# RTL-SDR.net
KiCad netlist of a schematic drawn in Altium Designer
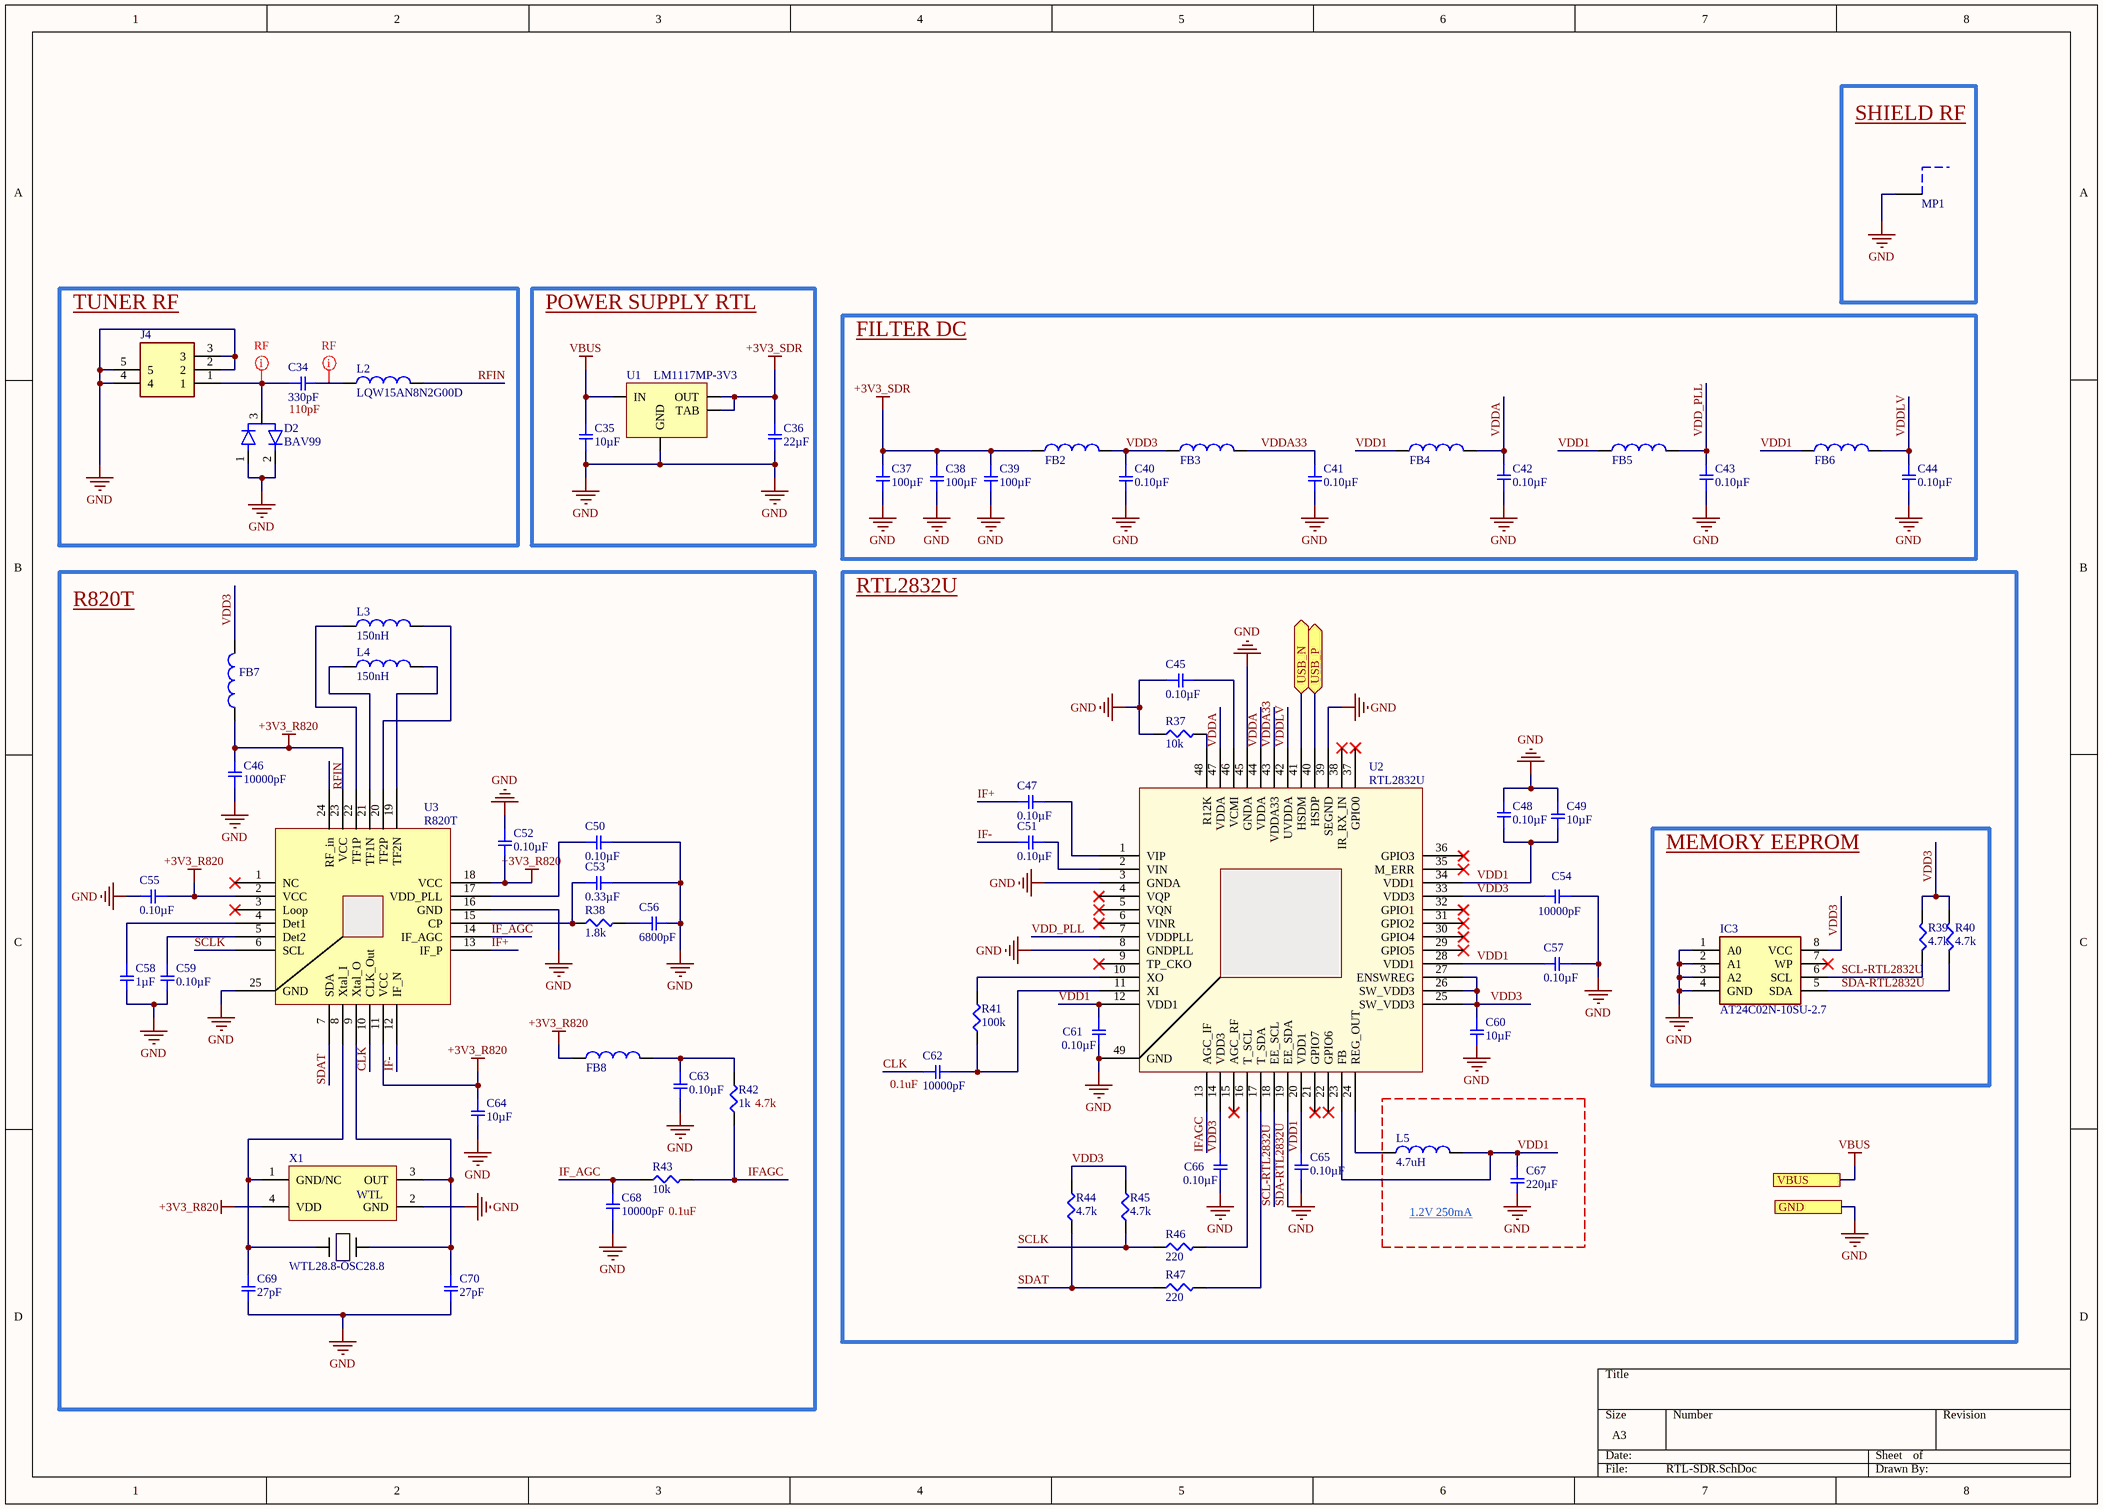
[diagram p0: RTL-SDR.SchDoc]

(export (version "E")
  (design (tool "Eeschema 10.0.6"))
  (components
    (comp (ref "C34")
      (value "330pF")
      (footprint "SMD-0402C")
      (description "CAP CER 330PF 25V NP0 0402")
      (fields
        (field (name "PART NUMBER") "GRM1555C1E331JA01D")
        (field (name "DIGI-KEY PART NUMBER") "490-8176-1-ND")
      )
      (libsource (lib "cap_murata") (part "CAPACITOR"))
    )
    (comp (ref "C35")
      (value "10µF")
      (footprint "SMD-0805C")
      (description "CAP CER 10UF 16V X6S 0805")
      (fields
        (field (name "PART NUMBER") "GRT21BC81C106KE01L")
        (field (name "DIGI-KEY PART NUMBER") "490-12343-1-ND")
      )
      (libsource (lib "cap_murata") (part "CAPACITOR"))
    )
    (comp (ref "C36")
      (value "22µF")
      (footprint "SMD-0805C")
      (description "CAP CER 22UF 16V X5R 0805")
      (fields
        (field (name "PART NUMBER") "GRT21BR61C226ME13L")
        (field (name "DIGI-KEY PART NUMBER") "490-12383-1-ND")
      )
      (libsource (lib "cap_murata") (part "CAPACITOR"))
    )
    (comp (ref "C37")
      (value "100µF")
      (footprint "SMD-1210C")
      (description "CAP CER 100UF 6.3V X7S 1210")
      (fields
        (field (name "PART NUMBER") "GRM32EC70J107ME15L")
        (field (name "DIGI-KEY PART NUMBER") "490-10530-1-ND")
      )
      (libsource (lib "cap_murata") (part "CAPACITOR"))
    )
    (comp (ref "C38")
      (value "100µF")
      (footprint "SMD-1210C")
      (description "CAP CER 100UF 6.3V X7S 1210")
      (fields
        (field (name "PART NUMBER") "GRM32EC70J107ME15L")
        (field (name "DIGI-KEY PART NUMBER") "490-10530-1-ND")
      )
      (libsource (lib "cap_murata") (part "CAPACITOR"))
    )
    (comp (ref "C39")
      (value "100µF")
      (footprint "SMD-1210C")
      (description "CAP CER 100UF 6.3V X7S 1210")
      (fields
        (field (name "PART NUMBER") "GRM32EC70J107ME15L")
        (field (name "DIGI-KEY PART NUMBER") "490-10530-1-ND")
      )
      (libsource (lib "cap_murata") (part "CAPACITOR"))
    )
    (comp (ref "C40")
      (value "0.10µF")
      (footprint "SMD-0402C")
      (description "CAP CER 0.1UF 16V X7R 0402")
      (fields
        (field (name "PART NUMBER") "GCM155R71C104KA55J")
        (field (name "DIGI-KEY PART NUMBER") "490-7998-1-ND")
      )
      (libsource (lib "cap_murata") (part "CAPACITOR"))
    )
    (comp (ref "C41")
      (value "0.10µF")
      (footprint "SMD-0402C")
      (description "CAP CER 0.1UF 16V X7R 0402")
      (fields
        (field (name "PART NUMBER") "GCM155R71C104KA55J")
        (field (name "DIGI-KEY PART NUMBER") "490-7998-1-ND")
      )
      (libsource (lib "cap_murata") (part "CAPACITOR"))
    )
    (comp (ref "C42")
      (value "0.10µF")
      (footprint "SMD-0402C")
      (description "CAP CER 0.1UF 16V X7R 0402")
      (fields
        (field (name "PART NUMBER") "GCM155R71C104KA55J")
        (field (name "DIGI-KEY PART NUMBER") "490-7998-1-ND")
      )
      (libsource (lib "cap_murata") (part "CAPACITOR"))
    )
    (comp (ref "C43")
      (value "0.10µF")
      (footprint "SMD-0402C")
      (description "CAP CER 0.1UF 16V X7R 0402")
      (fields
        (field (name "PART NUMBER") "GCM155R71C104KA55J")
        (field (name "DIGI-KEY PART NUMBER") "490-7998-1-ND")
      )
      (libsource (lib "cap_murata") (part "CAPACITOR"))
    )
    (comp (ref "C44")
      (value "0.10µF")
      (footprint "SMD-0402C")
      (description "CAP CER 0.1UF 16V X7R 0402")
      (fields
        (field (name "PART NUMBER") "GCM155R71C104KA55J")
        (field (name "DIGI-KEY PART NUMBER") "490-7998-1-ND")
      )
      (libsource (lib "cap_murata") (part "CAPACITOR"))
    )
    (comp (ref "C45")
      (value "0.10µF")
      (footprint "SMD-0402C")
      (description "CAP CER 0.1UF 16V X7R 0402")
      (fields
        (field (name "PART NUMBER") "GCM155R71C104KA55J")
        (field (name "DIGI-KEY PART NUMBER") "490-7998-1-ND")
      )
      (libsource (lib "cap_murata") (part "CAPACITOR"))
    )
    (comp (ref "C46")
      (value "10000pF")
      (footprint "SMD-0402C")
      (description "CAP CER 10000PF 16V X7R 0402")
      (fields
        (field (name "PART NUMBER") "GRM155R71C103KA01J")
        (field (name "DIGI-KEY PART NUMBER") "490-6326-1-ND")
      )
      (libsource (lib "cap_murata") (part "CAPACITOR"))
    )
    (comp (ref "C47")
      (value "0.10µF")
      (footprint "SMD-0402C")
      (description "CAP CER 0.1UF 16V X7R 0402")
      (fields
        (field (name "PART NUMBER") "GCM155R71C104KA55J")
        (field (name "DIGI-KEY PART NUMBER") "490-7998-1-ND")
      )
      (libsource (lib "cap_murata") (part "CAPACITOR"))
    )
    (comp (ref "C48")
      (value "0.10µF")
      (footprint "SMD-0402C")
      (description "CAP CER 0.1UF 16V X7R 0402")
      (fields
        (field (name "PART NUMBER") "GCM155R71C104KA55J")
        (field (name "DIGI-KEY PART NUMBER") "490-7998-1-ND")
      )
      (libsource (lib "cap_murata") (part "CAPACITOR"))
    )
    (comp (ref "C49")
      (value "10µF")
      (footprint "SMD-0603C")
      (description "CAP CER 10UF 16V X6S 0603")
      (fields
        (field (name "PART NUMBER") "GRT188C81C106ME13D")
        (field (name "DIGI-KEY PART NUMBER") "490-12286-1-ND")
      )
      (libsource (lib "cap_murata") (part "CAPACITOR"))
    )
    (comp (ref "C50")
      (value "0.10µF")
      (footprint "SMD-0402C")
      (description "CAP CER 0.1UF 16V X7R 0402")
      (fields
        (field (name "PART NUMBER") "GCM155R71C104KA55J")
        (field (name "DIGI-KEY PART NUMBER") "490-7998-1-ND")
      )
      (libsource (lib "cap_murata") (part "CAPACITOR"))
    )
    (comp (ref "C51")
      (value "0.10µF")
      (footprint "SMD-0402C")
      (description "CAP CER 0.1UF 16V X7R 0402")
      (fields
        (field (name "PART NUMBER") "GCM155R71C104KA55J")
        (field (name "DIGI-KEY PART NUMBER") "490-7998-1-ND")
      )
      (libsource (lib "cap_murata") (part "CAPACITOR"))
    )
    (comp (ref "C52")
      (value "0.10µF")
      (footprint "SMD-0402C")
      (description "CAP CER 0.1UF 16V X7R 0402")
      (fields
        (field (name "PART NUMBER") "GCM155R71C104KA55J")
        (field (name "DIGI-KEY PART NUMBER") "490-7998-1-ND")
      )
      (libsource (lib "cap_murata") (part "CAPACITOR"))
    )
    (comp (ref "C53")
      (value "0.33µF")
      (footprint "SMD-0402C")
      (description "CAP CER 0.33UF 10V X5R 0402")
      (fields
        (field (name "PART NUMBER") "GRM155R61A334KE15D")
        (field (name "DIGI-KEY PART NUMBER") "490-3263-1-ND")
      )
      (libsource (lib "cap_murata") (part "CAPACITOR"))
    )
    (comp (ref "C54")
      (value "10000pF")
      (footprint "SMD-0402C")
      (description "CAP CER 10000PF 16V X7R 0402")
      (fields
        (field (name "PART NUMBER") "GRM155R71C103KA01J")
        (field (name "DIGI-KEY PART NUMBER") "490-6326-1-ND")
      )
      (libsource (lib "cap_murata") (part "CAPACITOR"))
    )
    (comp (ref "C55")
      (value "0.10µF")
      (footprint "SMD-0402C")
      (description "CAP CER 0.1UF 16V X7R 0402")
      (fields
        (field (name "PART NUMBER") "GCM155R71C104KA55J")
        (field (name "DIGI-KEY PART NUMBER") "490-7998-1-ND")
      )
      (libsource (lib "cap_murata") (part "CAPACITOR"))
    )
    (comp (ref "C56")
      (value "6800pF")
      (footprint "SMD-0402C")
      (description "CAP CER 6800PF 25V X7R 0402")
      (fields
        (field (name "PART NUMBER") "GRM155R71E682KA01D")
        (field (name "DIGI-KEY PART NUMBER") "490-1310-1-ND")
      )
      (libsource (lib "cap_murata") (part "CAPACITOR"))
    )
    (comp (ref "C57")
      (value "0.10µF")
      (footprint "SMD-0402C")
      (description "CAP CER 0.1UF 16V X7R 0402")
      (fields
        (field (name "PART NUMBER") "GCM155R71C104KA55J")
        (field (name "DIGI-KEY PART NUMBER") "490-7998-1-ND")
      )
      (libsource (lib "cap_murata") (part "CAPACITOR"))
    )
    (comp (ref "C58")
      (value "1µF")
      (footprint "SMD-0402C")
      (description "CAP CER 1UF 25V X5R 0402")
      (fields
        (field (name "PART NUMBER") "GRM155R61E105MA12D")
        (field (name "DIGI-KEY PART NUMBER") "490-10018-1-ND")
      )
      (libsource (lib "cap_murata") (part "CAPACITOR"))
    )
    (comp (ref "C59")
      (value "0.10µF")
      (footprint "SMD-0402C")
      (description "CAP CER 0.1UF 16V X7R 0402")
      (fields
        (field (name "PART NUMBER") "GCM155R71C104KA55J")
        (field (name "DIGI-KEY PART NUMBER") "490-7998-1-ND")
      )
      (libsource (lib "cap_murata") (part "CAPACITOR"))
    )
    (comp (ref "C60")
      (value "10µF")
      (footprint "SMD-0603C")
      (description "CAP CER 10UF 16V X6S 0603")
      (fields
        (field (name "PART NUMBER") "GRT188C81C106ME13D")
        (field (name "DIGI-KEY PART NUMBER") "490-12286-1-ND")
      )
      (libsource (lib "cap_murata") (part "CAPACITOR"))
    )
    (comp (ref "C61")
      (value "0.10µF")
      (footprint "SMD-0402C")
      (description "CAP CER 0.1UF 16V X7R 0402")
      (fields
        (field (name "PART NUMBER") "GCM155R71C104KA55J")
        (field (name "DIGI-KEY PART NUMBER") "490-7998-1-ND")
      )
      (libsource (lib "cap_murata") (part "CAPACITOR"))
    )
    (comp (ref "C62")
      (value "10000pF")
      (footprint "SMD-0402C")
      (description "CAP CER 10000PF 16V X7R 0402")
      (fields
        (field (name "PART NUMBER") "GRM155R71C103KA01D")
        (field (name "DIGI-KEY PART NUMBER") "490-1313-1-ND")
      )
      (libsource (lib "cap_murata") (part "CAPACITOR"))
    )
    (comp (ref "C63")
      (value "0.10µF")
      (footprint "SMD-0402C")
      (description "CAP CER 0.1UF 16V X7R 0402")
      (fields
        (field (name "PART NUMBER") "GCM155R71C104KA55J")
        (field (name "DIGI-KEY PART NUMBER") "490-7998-1-ND")
      )
      (libsource (lib "cap_murata") (part "CAPACITOR"))
    )
    (comp (ref "C64")
      (value "10µF")
      (footprint "SMD-0805C")
      (description "CAP CER 10UF 16V X6S 0805")
      (fields
        (field (name "PART NUMBER") "GRT21BC81C106KE01L")
        (field (name "DIGI-KEY PART NUMBER") "490-12343-1-ND")
      )
      (libsource (lib "cap_murata") (part "CAPACITOR"))
    )
    (comp (ref "C65")
      (value "0.10µF")
      (footprint "SMD-0402C")
      (description "CAP CER 0.1UF 16V X7R 0402")
      (fields
        (field (name "PART NUMBER") "GCM155R71C104KA55J")
        (field (name "DIGI-KEY PART NUMBER") "490-7998-1-ND")
      )
      (libsource (lib "cap_murata") (part "CAPACITOR"))
    )
    (comp (ref "C66")
      (value "0.10µF")
      (footprint "SMD-0402C")
      (description "CAP CER 0.1UF 16V X7R 0402")
      (fields
        (field (name "PART NUMBER") "GCM155R71C104KA55J")
        (field (name "DIGI-KEY PART NUMBER") "490-7998-1-ND")
      )
      (libsource (lib "cap_murata") (part "CAPACITOR"))
    )
    (comp (ref "C67")
      (value "220µF")
      (footprint "SMD-1210C")
      (description "CAP CER 220UF 4V X6S 1210")
      (fields
        (field (name "PART NUMBER") "GRM32EC80G227ME05L")
        (field (name "DIGI-KEY PART NUMBER") "490-13973-1-ND")
      )
      (libsource (lib "cap_murata") (part "CAPACITOR"))
    )
    (comp (ref "C68")
      (value "10000pF")
      (footprint "SMD-0402C")
      (description "CAP CER 10000PF 16V X7R 0402")
      (fields
        (field (name "PART NUMBER") "GRM155R71C103KA01J")
        (field (name "DIGI-KEY PART NUMBER") "490-6326-1-ND")
      )
      (libsource (lib "cap_murata") (part "CAPACITOR"))
    )
    (comp (ref "C69")
      (value "27pF")
      (footprint "SMD-0402C")
      (description "CAP CER 27PF 25V NP0 0402")
      (fields
        (field (name "PART NUMBER") "GRM1555C1E270JA01D")
        (field (name "DIGI-KEY PART NUMBER") "490-6176-1-ND")
      )
      (libsource (lib "cap_murata") (part "CAPACITOR"))
    )
    (comp (ref "C70")
      (value "27pF")
      (footprint "SMD-0402C")
      (description "CAP CER 27PF 25V NP0 0402")
      (fields
        (field (name "PART NUMBER") "GRM1555C1E270JA01D")
        (field (name "DIGI-KEY PART NUMBER") "490-6176-1-ND")
      )
      (libsource (lib "cap_murata") (part "CAPACITOR"))
    )
    (comp (ref "D2")
      (value "BAV99")
      (footprint "DIO_BAV99")
      (fields (field (name "MF") "ON Semiconductor"))
      (libsource (lib "DSD_Aerobits_RPI4_OLED") (part "BAV99"))
    )
    (comp (ref "FB2")
      (value "10Ohm")
      (footprint "WE-CBA_0402_L1W0.5H0.5_HC")
      (description "WE-CBA SMT EMI Suppression Ferrite Bead, size 0402, 10Ohm, 1.5A")
      (fields
        (field (name "MANUFACTURER PART NUMBER") "782423100")
        (field (name "MANUFACTURER") "Wurth Elektronik")
      )
      (libsource (lib "Altium_WE-CBA (rev22d)") (part "782423100"))
    )
    (comp (ref "FB3")
      (value "10Ohm")
      (footprint "WE-CBA_0402_L1W0.5H0.5_HC")
      (description "WE-CBA SMT EMI Suppression Ferrite Bead, size 0402, 10Ohm, 1.5A")
      (fields
        (field (name "MANUFACTURER PART NUMBER") "782423100")
        (field (name "MANUFACTURER") "Wurth Elektronik")
      )
      (libsource (lib "Altium_WE-CBA (rev22d)") (part "782423100"))
    )
    (comp (ref "FB4")
      (value "10Ohm")
      (footprint "WE-CBA_0402_L1W0.5H0.5_HC")
      (description "WE-CBA SMT EMI Suppression Ferrite Bead, size 0402, 10Ohm, 1.5A")
      (fields
        (field (name "MANUFACTURER PART NUMBER") "782423100")
        (field (name "MANUFACTURER") "Wurth Elektronik")
      )
      (libsource (lib "Altium_WE-CBA (rev22d)") (part "782423100"))
    )
    (comp (ref "FB5")
      (value "10Ohm")
      (footprint "WE-CBA_0402_L1W0.5H0.5_HC")
      (description "WE-CBA SMT EMI Suppression Ferrite Bead, size 0402, 10Ohm, 1.5A")
      (fields
        (field (name "MANUFACTURER PART NUMBER") "782423100")
        (field (name "MANUFACTURER") "Wurth Elektronik")
      )
      (libsource (lib "Altium_WE-CBA (rev22d)") (part "782423100"))
    )
    (comp (ref "FB6")
      (value "10Ohm")
      (footprint "WE-CBA_0402_L1W0.5H0.5_HC")
      (description "WE-CBA SMT EMI Suppression Ferrite Bead, size 0402, 10Ohm, 1.5A")
      (fields
        (field (name "MANUFACTURER PART NUMBER") "782423100")
        (field (name "MANUFACTURER") "Wurth Elektronik")
      )
      (libsource (lib "Altium_WE-CBA (rev22d)") (part "782423100"))
    )
    (comp (ref "FB7")
      (value "10Ohm")
      (footprint "WE-CBA_0402_L1W0.5H0.5_HC")
      (description "WE-CBA SMT EMI Suppression Ferrite Bead, size 0402, 10Ohm, 1.5A")
      (fields
        (field (name "MANUFACTURER PART NUMBER") "782423100")
        (field (name "MANUFACTURER") "Wurth Elektronik")
      )
      (libsource (lib "Altium_WE-CBA (rev22d)") (part "782423100"))
    )
    (comp (ref "FB8")
      (value "10Ohm")
      (footprint "WE-CBA_0402_L1W0.5H0.5_HC")
      (description "WE-CBA SMT EMI Suppression Ferrite Bead, size 0402, 10Ohm, 1.5A")
      (fields
        (field (name "MANUFACTURER PART NUMBER") "782423100")
        (field (name "MANUFACTURER") "Wurth Elektronik")
      )
      (libsource (lib "Altium_WE-CBA (rev22d)") (part "782423100"))
    )
    (comp (ref "IC3")
      (value "AT24C02N-10SU-2.7")
      (footprint "SamacSys:SOIC127P600X175-8N")
      (description "Integrated Circuit")
      (libsource (lib "SamacSys") (part "AT24C02N-10SU-2.7"))
    )
    (comp (ref "J4")
      (value "SMA-J-P-H-RA-TH1")
      (footprint "SamacSys:SMAJPHRATH1")
      (description "Connector")
      (fields (field (name "MOUSER PART NUMBER") "200-SMAJPHRATH1"))
      (libsource (lib "*") (part "SMA-J-P-H-RA-TH1"))
    )
    (comp (ref "L2")
      (value "LQW15AN8N2G00D")
      (footprint "INDC1006X60N")
      (description "LQW15A 0,0082ÂµH 540mA 2% WWT")
      (libsource (lib "DSD_Aerobits_RPI4_OLED") (part "LQW15AN8N2G00D"))
    )
    (comp (ref "L3")
      (value "150nH")
      (footprint "INDC1608X100N")
      (description "CHIP COIL LQW18A")
      (fields (field (name "MP") "LQW18ANR15J00D"))
      (libsource (lib "DSD_Aerobits_RPI4_OLED") (part "LQW18ANR15J00D"))
    )
    (comp (ref "L4")
      (value "150nH")
      (footprint "INDC1608X100N")
      (description "CHIP COIL LQW18A")
      (fields (field (name "MP") "LQW18ANR15J00D"))
      (libsource (lib "DSD_Aerobits_RPI4_OLED") (part "LQW18ANR15J00D"))
    )
    (comp (ref "L5")
      (value "4.7uH")
      (footprint "INDC2518X200N")
      (description "Ind Power Chip Wirewound 4.7uH 20% 7.96MHz Ferrite 1.1A 1007 T/R")
      (fields (field (name "MP") "CB2518T4R7M"))
      (libsource (lib "DSD_Aerobits_RPI4_OLED") (part "CB2518T4R7M"))
    )
    (comp (ref "MP1")
      (value "36903205S")
      (footprint "36903205S")
      (description "WE-SHC Shielding Cabinet, One Piece, Tin Plated, Tape and Reel, 20x20x3mm")
      (fields (field (name "MANUFACTURER") "Wurth Elektronik"))
      (libsource (lib "WE-SHC (rev22a) (1)") (part "36903205S"))
    )
    (comp (ref "R37")
      (value "10k")
      (footprint "SMD-0402-RES")
      (description "RES SMD 10K OHM 1% 1/10W 0402")
      (fields
        (field (name "PART NUMBER") "ERJ-2RKF1002X")
        (field (name "DIGI-KEY PART NUMBER") "P10.0KLCT-ND")
      )
      (libsource (lib "res_panasonic_erj_xls") (part "RESISTOR"))
    )
    (comp (ref "R38")
      (value "1.8k")
      (footprint "SMD-0402-RES")
      (description "RES SMD 1.8K OHM 5% 1/10W 0402")
      (fields (field (name "PART NUMBER") "ERJ-2GEJ182X") (field (name "DIGI-KEY PART NUMBER") "P1.8KJCT-ND"))
      (libsource (lib "res_panasonic_erj_xls") (part "RESISTOR"))
    )
    (comp (ref "R39")
      (value "4.7k")
      (footprint "SMD-0402-RES")
      (description "RES SMD 4.7K OHM 1% 1/10W 0402")
      (fields
        (field (name "PART NUMBER") "ERJ-2RKF4701X")
        (field (name "DIGI-KEY PART NUMBER") "P4.70KLCT-ND")
      )
      (libsource (lib "res_panasonic_erj_xls") (part "RESISTOR"))
    )
    (comp (ref "R40")
      (value "4.7k")
      (footprint "SMD-0402-RES")
      (description "RES SMD 4.7K OHM 1% 1/10W 0402")
      (fields
        (field (name "PART NUMBER") "ERJ-2RKF4701X")
        (field (name "DIGI-KEY PART NUMBER") "P4.70KLCT-ND")
      )
      (libsource (lib "res_panasonic_erj_xls") (part "RESISTOR"))
    )
    (comp (ref "R41")
      (value "100k")
      (footprint "SMD-0402-RES")
      (description "RES SMD 100K OHM 1% 1/10W 0402")
      (fields
        (field (name "PART NUMBER") "ERJ-2RKF1003X")
        (field (name "DIGI-KEY PART NUMBER") "P100KLCT-ND")
      )
      (libsource (lib "res_panasonic_erj_xls") (part "RESISTOR"))
    )
    (comp (ref "R42")
      (value "1k")
      (footprint "SMD-0402-RES")
      (description "RES SMD 1K OHM 5% 1/10W 0402")
      (fields (field (name "PART NUMBER") "ERJ-2GEJ102X") (field (name "DIGI-KEY PART NUMBER") "P1.0KJCT-ND"))
      (libsource (lib "res_panasonic_erj_xls") (part "RESISTOR"))
    )
    (comp (ref "R43")
      (value "10k")
      (footprint "SMD-0402-RES")
      (description "RES SMD 10K OHM 1% 1/10W 0402")
      (fields
        (field (name "PART NUMBER") "ERJ-2RKF1002X")
        (field (name "DIGI-KEY PART NUMBER") "P10.0KLCT-ND")
      )
      (libsource (lib "res_panasonic_erj_xls") (part "RESISTOR"))
    )
    (comp (ref "R44")
      (value "4.7k")
      (footprint "SMD-0402-RES")
      (description "RES SMD 4.7K OHM 1% 1/10W 0402")
      (fields
        (field (name "PART NUMBER") "ERJ-2RKF4701X")
        (field (name "DIGI-KEY PART NUMBER") "P4.70KLCT-ND")
      )
      (libsource (lib "res_panasonic_erj_xls") (part "RESISTOR"))
    )
    (comp (ref "R45")
      (value "4.7k")
      (footprint "SMD-0402-RES")
      (description "RES SMD 4.7K OHM 1% 1/10W 0402")
      (fields
        (field (name "PART NUMBER") "ERJ-2RKF4701X")
        (field (name "DIGI-KEY PART NUMBER") "P4.70KLCT-ND")
      )
      (libsource (lib "res_panasonic_erj_xls") (part "RESISTOR"))
    )
    (comp (ref "R46")
      (value "220")
      (footprint "SMD-0402-RES")
      (description "RES SMD 220 OHM 5% 1/5W 0402")
      (fields (field (name "PART NUMBER") "ERJ-PA2J221X") (field (name "DIGI-KEY PART NUMBER") "P17189CT-ND"))
      (libsource (lib "res_panasonic_erj_xls") (part "RESISTOR"))
    )
    (comp (ref "R47")
      (value "220")
      (footprint "SMD-0402-RES")
      (description "RES SMD 220 OHM 5% 1/5W 0402")
      (fields (field (name "PART NUMBER") "ERJ-PA2J221X") (field (name "DIGI-KEY PART NUMBER") "P17189CT-ND"))
      (libsource (lib "res_panasonic_erj_xls") (part "RESISTOR"))
    )
    (comp (ref "U1")
      (value "LM1117MP-3V3")
      (footprint "SOT223")
      (description "800mA Low-Dropout Linear Regulator")
      (fields
        (field (name "PARTNUMBER") "LM1117MP-3.3")
        (field (name "MANUFACTURER") "National Semiconductor")
        (field (name "PUBLISHER") "Altium Limited")
      )
      (libsource (lib "biblioteka_schematic") (part "LM1117MP-3V3"))
    )
    (comp (ref "U2")
      (value "RTL2832U")
      (footprint "QFN40P600X600X84_HS-49N")
      (description "RTL2832U DVB-T COFDM Demodulator + USB 2.0")
      (fields (field (name "MANUFACTURER") "Realtek") (field (name "PUBLISHER") "ftg"))
      (libsource (lib "DSD_Aerobits_RPI4_OLED") (part "RTL2832U"))
    )
    (comp (ref "U3")
      (value "R820T")
      (footprint "QFN50P400X400X85_HS-25N_r820t")
      (libsource (lib "DSD_Aerobits_RPI4_OLED") (part "R820T"))
    )
    (comp (ref "X1")
      (value "WTL28.8-OSC28.8")
      (footprint "WTL28.8-OSC28.8")
      (libsource (lib "DSD_Aerobits_RPI4_OLED") (part "WTL28.8-OSC28.8"))
    )
  )
  (nets
    (net (code "1") (name "+3V3_R820") (class "Default")
      (node (ref "C46") (pin "2") (pinfunction "2_2") (pintype "passive"))
      (node (ref "C52") (pin "2") (pinfunction "2_2") (pintype "passive"))
      (node (ref "C55") (pin "1") (pinfunction "1_1") (pintype "passive"))
      (node (ref "C64") (pin "1") (pinfunction "1_1") (pintype "passive"))
      (node (ref "FB7") (pin "1") (pinfunction "1_1") (pintype "passive"))
      (node (ref "FB8") (pin "1") (pinfunction "1_1") (pintype "passive"))
      (node (ref "U3") (pin "11") (pinfunction "VCC_11") (pintype "passive"))
      (node (ref "U3") (pin "18") (pinfunction "VCC_18") (pintype "passive"))
      (node (ref "U3") (pin "2") (pinfunction "VCC_2") (pintype "passive"))
      (node (ref "U3") (pin "23") (pinfunction "VCC_23") (pintype "passive"))
      (node (ref "X1") (pin "4") (pinfunction "VDD_4") (pintype "passive"))
    )
    (net (code "2") (name "+3V3_SDR") (class "Default")
      (node (ref "C36") (pin "2") (pinfunction "2_2") (pintype "passive"))
      (node (ref "C37") (pin "1") (pinfunction "1_1") (pintype "passive"))
      (node (ref "C38") (pin "1") (pinfunction "1_1") (pintype "passive"))
      (node (ref "C39") (pin "1") (pinfunction "1_1") (pintype "passive"))
      (node (ref "FB2") (pin "1") (pinfunction "1_1") (pintype "passive"))
      (node (ref "U1") (pin "2") (pinfunction "OUT_2") (pintype "power_in"))
      (node (ref "U1") (pin "4") (pinfunction "TAB_4") (pintype "power_in"))
    )
    (net (code "3") (name "/CLK") (class "Default")
      (node (ref "C62") (pin "1") (pinfunction "1_1") (pintype "passive"))
      (node (ref "U3") (pin "10") (pinfunction "CLK_Out_10") (pintype "passive"))
    )
    (net (code "4") (name "/IF+") (class "Default")
      (node (ref "C47") (pin "2") (pinfunction "2_2") (pintype "passive"))
      (node (ref "U3") (pin "13") (pinfunction "IF_P_13") (pintype "passive"))
    )
    (net (code "5") (name "/IF-") (class "Default")
      (node (ref "C51") (pin "2") (pinfunction "2_2") (pintype "passive"))
      (node (ref "U3") (pin "12") (pinfunction "IF_N_12") (pintype "passive"))
    )
    (net (code "6") (name "/IFAGC") (class "Default")
      (node (ref "R42") (pin "1") (pinfunction "1_1") (pintype "passive"))
      (node (ref "R43") (pin "2") (pinfunction "2_2") (pintype "passive"))
      (node (ref "U2") (pin "13") (pinfunction "AGC_IF_13") (pintype "passive"))
    )
    (net (code "7") (name "/IF_AGC") (class "Default")
      (node (ref "C68") (pin "2") (pinfunction "2_2") (pintype "passive"))
      (node (ref "R43") (pin "1") (pinfunction "1_1") (pintype "passive"))
      (node (ref "U3") (pin "14") (pinfunction "IF_AGC_14") (pintype "passive"))
    )
    (net (code "8") (name "/RFIN") (class "Default")
      (node (ref "L2") (pin "2") (pinfunction "2_2") (pintype "passive"))
      (node (ref "U3") (pin "24") (pinfunction "RF_in_24") (pintype "passive"))
    )
    (net (code "9") (name "/SCL-RTL2832U") (class "Default")
      (node (ref "IC3") (pin "6") (pinfunction "SCL_6") (pintype "passive"))
      (node (ref "R39") (pin "1") (pinfunction "1_1") (pintype "passive"))
      (node (ref "U2") (pin "18") (pinfunction "EE_SCL_18") (pintype "passive"))
    )
    (net (code "10") (name "/SCLK") (class "Default")
      (node (ref "R45") (pin "1") (pinfunction "1_1") (pintype "passive"))
      (node (ref "R46") (pin "1") (pinfunction "1_1") (pintype "passive"))
      (node (ref "U3") (pin "6") (pinfunction "SCL_6") (pintype "passive"))
    )
    (net (code "11") (name "/SDA-RTL2832U") (class "Default")
      (node (ref "IC3") (pin "5") (pinfunction "SDA_5") (pintype "passive"))
      (node (ref "R40") (pin "1") (pinfunction "1_1") (pintype "passive"))
      (node (ref "U2") (pin "19") (pinfunction "EE_SDA_19") (pintype "passive"))
    )
    (net (code "12") (name "/SDAT") (class "Default")
      (node (ref "R44") (pin "1") (pinfunction "1_1") (pintype "passive"))
      (node (ref "R47") (pin "1") (pinfunction "1_1") (pintype "passive"))
      (node (ref "U3") (pin "7") (pinfunction "SDA_7") (pintype "passive"))
    )
    (net (code "13") (name "/USB_N") (class "Default")
      (node (ref "U2") (pin "41") (pinfunction "HSDM_41") (pintype "passive"))
    )
    (net (code "14") (name "/USB_P") (class "Default")
      (node (ref "U2") (pin "40") (pinfunction "HSDP_40") (pintype "passive"))
    )
    (net (code "15") (name "/VDD1") (class "Default")
      (node (ref "C48") (pin "1") (pinfunction "1_1") (pintype "passive"))
      (node (ref "C49") (pin "2") (pinfunction "2_2") (pintype "passive"))
      (node (ref "C57") (pin "2") (pinfunction "2_2") (pintype "passive"))
      (node (ref "C61") (pin "1") (pinfunction "1_1") (pintype "passive"))
      (node (ref "C65") (pin "1") (pinfunction "1_1") (pintype "passive"))
      (node (ref "C67") (pin "1") (pinfunction "1_1") (pintype "passive"))
      (node (ref "FB4") (pin "1") (pinfunction "1_1") (pintype "passive"))
      (node (ref "FB5") (pin "1") (pinfunction "1_1") (pintype "passive"))
      (node (ref "FB6") (pin "1") (pinfunction "1_1") (pintype "passive"))
      (node (ref "L5") (pin "2") (pinfunction "2_2") (pintype "passive"))
      (node (ref "U2") (pin "12") (pinfunction "VDD1_12") (pintype "passive"))
      (node (ref "U2") (pin "20") (pinfunction "VDD1_20") (pintype "passive"))
      (node (ref "U2") (pin "23") (pinfunction "FB_23") (pintype "passive"))
      (node (ref "U2") (pin "28") (pinfunction "VDD1_28") (pintype "passive"))
      (node (ref "U2") (pin "34") (pinfunction "VDD1_34") (pintype "passive"))
    )
    (net (code "16") (name "/VDD3") (class "Default")
      (node (ref "C40") (pin "1") (pinfunction "1_1") (pintype "passive"))
      (node (ref "C54") (pin "2") (pinfunction "2_2") (pintype "passive"))
      (node (ref "C60") (pin "1") (pinfunction "1_1") (pintype "passive"))
      (node (ref "C66") (pin "1") (pinfunction "1_1") (pintype "passive"))
      (node (ref "FB2") (pin "2") (pinfunction "2_2") (pintype "passive"))
      (node (ref "FB3") (pin "1") (pinfunction "1_1") (pintype "passive"))
      (node (ref "FB7") (pin "2") (pinfunction "2_2") (pintype "passive"))
      (node (ref "IC3") (pin "8") (pinfunction "VCC_8") (pintype "passive"))
      (node (ref "R39") (pin "2") (pinfunction "2_2") (pintype "passive"))
      (node (ref "R40") (pin "2") (pinfunction "2_2") (pintype "passive"))
      (node (ref "R44") (pin "2") (pinfunction "2_2") (pintype "passive"))
      (node (ref "R45") (pin "2") (pinfunction "2_2") (pintype "passive"))
      (node (ref "U2") (pin "14") (pinfunction "VDD3_14") (pintype "passive"))
      (node (ref "U2") (pin "25") (pinfunction "SW_VDD3_25") (pintype "passive"))
      (node (ref "U2") (pin "26") (pinfunction "SW_VDD3_26") (pintype "passive"))
      (node (ref "U2") (pin "27") (pinfunction "ENSWREG_27") (pintype "passive"))
      (node (ref "U2") (pin "33") (pinfunction "VDD3_33") (pintype "passive"))
    )
    (net (code "17") (name "/VDDA") (class "Default")
      (node (ref "C42") (pin "2") (pinfunction "2_2") (pintype "passive"))
      (node (ref "FB4") (pin "2") (pinfunction "2_2") (pintype "passive"))
      (node (ref "U2") (pin "44") (pinfunction "VDDA_44") (pintype "passive"))
      (node (ref "U2") (pin "47") (pinfunction "VDDA_47") (pintype "passive"))
    )
    (net (code "18") (name "/VDDA33") (class "Default")
      (node (ref "C41") (pin "1") (pinfunction "1_1") (pintype "passive"))
      (node (ref "FB3") (pin "2") (pinfunction "2_2") (pintype "passive"))
      (node (ref "U2") (pin "43") (pinfunction "VDDA33_43") (pintype "passive"))
    )
    (net (code "19") (name "/VDDLV") (class "Default")
      (node (ref "C44") (pin "2") (pinfunction "2_2") (pintype "passive"))
      (node (ref "FB6") (pin "2") (pinfunction "2_2") (pintype "passive"))
      (node (ref "U2") (pin "42") (pinfunction "UVDDA_42") (pintype "passive"))
    )
    (net (code "20") (name "/VDD_PLL") (class "Default")
      (node (ref "C43") (pin "2") (pinfunction "2_2") (pintype "passive"))
      (node (ref "FB5") (pin "2") (pinfunction "2_2") (pintype "passive"))
      (node (ref "U2") (pin "7") (pinfunction "VDDPLL_7") (pintype "passive"))
    )
    (net (code "21") (name "GND") (class "Default")
      (node (ref "C35") (pin "1") (pinfunction "1_1") (pintype "passive"))
      (node (ref "C36") (pin "1") (pinfunction "1_1") (pintype "passive"))
      (node (ref "C37") (pin "2") (pinfunction "2_2") (pintype "passive"))
      (node (ref "C38") (pin "2") (pinfunction "2_2") (pintype "passive"))
      (node (ref "C39") (pin "2") (pinfunction "2_2") (pintype "passive"))
      (node (ref "C40") (pin "2") (pinfunction "2_2") (pintype "passive"))
      (node (ref "C41") (pin "2") (pinfunction "2_2") (pintype "passive"))
      (node (ref "C42") (pin "1") (pinfunction "1_1") (pintype "passive"))
      (node (ref "C43") (pin "1") (pinfunction "1_1") (pintype "passive"))
      (node (ref "C44") (pin "1") (pinfunction "1_1") (pintype "passive"))
      (node (ref "C45") (pin "1") (pinfunction "1_1") (pintype "passive"))
      (node (ref "C46") (pin "1") (pinfunction "1_1") (pintype "passive"))
      (node (ref "C48") (pin "2") (pinfunction "2_2") (pintype "passive"))
      (node (ref "C49") (pin "1") (pinfunction "1_1") (pintype "passive"))
      (node (ref "C50") (pin "1") (pinfunction "1_1") (pintype "passive"))
      (node (ref "C52") (pin "1") (pinfunction "1_1") (pintype "passive"))
      (node (ref "C53") (pin "1") (pinfunction "1_1") (pintype "passive"))
      (node (ref "C54") (pin "1") (pinfunction "1_1") (pintype "passive"))
      (node (ref "C55") (pin "2") (pinfunction "2_2") (pintype "passive"))
      (node (ref "C56") (pin "2") (pinfunction "2_2") (pintype "passive"))
      (node (ref "C57") (pin "1") (pinfunction "1_1") (pintype "passive"))
      (node (ref "C58") (pin "2") (pinfunction "2_2") (pintype "passive"))
      (node (ref "C59") (pin "2") (pinfunction "2_2") (pintype "passive"))
      (node (ref "C60") (pin "2") (pinfunction "2_2") (pintype "passive"))
      (node (ref "C61") (pin "2") (pinfunction "2_2") (pintype "passive"))
      (node (ref "C63") (pin "2") (pinfunction "2_2") (pintype "passive"))
      (node (ref "C64") (pin "2") (pinfunction "2_2") (pintype "passive"))
      (node (ref "C65") (pin "2") (pinfunction "2_2") (pintype "passive"))
      (node (ref "C66") (pin "2") (pinfunction "2_2") (pintype "passive"))
      (node (ref "C67") (pin "2") (pinfunction "2_2") (pintype "passive"))
      (node (ref "C68") (pin "1") (pinfunction "1_1") (pintype "passive"))
      (node (ref "C69") (pin "2") (pinfunction "2_2") (pintype "passive"))
      (node (ref "C70") (pin "2") (pinfunction "2_2") (pintype "passive"))
      (node (ref "D2") (pin "1") (pinfunction "1_1") (pintype "passive"))
      (node (ref "D2") (pin "2") (pinfunction "2_2") (pintype "passive"))
      (node (ref "IC3") (pin "1") (pinfunction "A0_1") (pintype "passive"))
      (node (ref "IC3") (pin "2") (pinfunction "A1_2") (pintype "passive"))
      (node (ref "IC3") (pin "3") (pinfunction "A2_3") (pintype "passive"))
      (node (ref "IC3") (pin "4") (pinfunction "GND_4") (pintype "passive"))
      (node (ref "J4") (pin "2") (pinfunction "2_2") (pintype "passive"))
      (node (ref "J4") (pin "3") (pinfunction "3_3") (pintype "passive"))
      (node (ref "J4") (pin "4") (pinfunction "4_4") (pintype "passive"))
      (node (ref "J4") (pin "5") (pinfunction "5_5") (pintype "passive"))
      (node (ref "MP1") (pin "1") (pinfunction "1_1") (pintype "passive"))
      (node (ref "R37") (pin "1") (pinfunction "1_1") (pintype "passive"))
      (node (ref "U1") (pin "1") (pinfunction "GND_1") (pintype "power_in"))
      (node (ref "U2") (pin "3") (pinfunction "GNDA_3") (pintype "passive"))
      (node (ref "U2") (pin "39") (pinfunction "SEGND_39") (pintype "passive"))
      (node (ref "U2") (pin "45") (pinfunction "GNDA_45") (pintype "passive"))
      (node (ref "U2") (pin "49") (pinfunction "GND_49") (pintype "passive"))
      (node (ref "U2") (pin "8") (pinfunction "GNDPLL_8") (pintype "passive"))
      (node (ref "U3") (pin "16") (pinfunction "GND_16") (pintype "passive"))
      (node (ref "U3") (pin "25") (pinfunction "GND_25") (pintype "passive"))
      (node (ref "X1") (pin "2") (pinfunction "GND_2") (pintype "passive"))
    )
    (net (code "22") (name "Net-(C34-Pad1)") (class "Default")
      (node (ref "C34") (pin "1") (pinfunction "1_1") (pintype "passive"))
      (node (ref "D2") (pin "3") (pinfunction "3_3") (pintype "passive"))
      (node (ref "J4") (pin "1") (pinfunction "1_1") (pintype "passive"))
    )
    (net (code "23") (name "Net-(C34-Pad2)") (class "Default")
      (node (ref "C34") (pin "2") (pinfunction "2_2") (pintype "passive"))
      (node (ref "L2") (pin "1") (pinfunction "1_1") (pintype "passive"))
    )
    (net (code "24") (name "Net-(C56-Pad1)") (class "Default")
      (node (ref "C56") (pin "1") (pinfunction "1_1") (pintype "passive"))
      (node (ref "R38") (pin "2") (pinfunction "2_2") (pintype "passive"))
    )
    (net (code "25") (name "Net-(C63-Pad1)") (class "Default")
      (node (ref "C63") (pin "1") (pinfunction "1_1") (pintype "passive"))
      (node (ref "FB8") (pin "2") (pinfunction "2_2") (pintype "passive"))
      (node (ref "R42") (pin "2") (pinfunction "2_2") (pintype "passive"))
    )
    (net (code "26") (name "Net-(U2-R12K)") (class "Default")
      (node (ref "R37") (pin "2") (pinfunction "2_2") (pintype "passive"))
      (node (ref "U2") (pin "48") (pinfunction "R12K_48") (pintype "passive"))
    )
    (net (code "27") (name "Net-(U2-REG_OUT)") (class "Default")
      (node (ref "L5") (pin "1") (pinfunction "1_1") (pintype "passive"))
      (node (ref "U2") (pin "24") (pinfunction "REG_OUT_24") (pintype "passive"))
    )
    (net (code "28") (name "Net-(U2-T_SCL)") (class "Default")
      (node (ref "R46") (pin "2") (pinfunction "2_2") (pintype "passive"))
      (node (ref "U2") (pin "16") (pinfunction "T_SCL_16") (pintype "passive"))
    )
    (net (code "29") (name "Net-(U2-T_SDA)") (class "Default")
      (node (ref "R47") (pin "2") (pinfunction "2_2") (pintype "passive"))
      (node (ref "U2") (pin "17") (pinfunction "T_SDA_17") (pintype "passive"))
    )
    (net (code "30") (name "Net-(U2-VCMI)") (class "Default")
      (node (ref "C45") (pin "2") (pinfunction "2_2") (pintype "passive"))
      (node (ref "U2") (pin "46") (pinfunction "VCMI_46") (pintype "passive"))
    )
    (net (code "31") (name "Net-(U2-VIN)") (class "Default")
      (node (ref "C51") (pin "1") (pinfunction "1_1") (pintype "passive"))
      (node (ref "U2") (pin "2") (pinfunction "VIN_2") (pintype "passive"))
    )
    (net (code "32") (name "Net-(U2-VIP)") (class "Default")
      (node (ref "C47") (pin "1") (pinfunction "1_1") (pintype "passive"))
      (node (ref "U2") (pin "1") (pinfunction "VIP_1") (pintype "passive"))
    )
    (net (code "33") (name "Net-(U2-XI)") (class "Default")
      (node (ref "C62") (pin "2") (pinfunction "2_2") (pintype "passive"))
      (node (ref "R41") (pin "1") (pinfunction "1_1") (pintype "passive"))
      (node (ref "U2") (pin "11") (pinfunction "XI_11") (pintype "passive"))
    )
    (net (code "34") (name "Net-(U2-XO)") (class "Default")
      (node (ref "R41") (pin "2") (pinfunction "2_2") (pintype "passive"))
      (node (ref "U2") (pin "10") (pinfunction "XO_10") (pintype "passive"))
    )
    (net (code "35") (name "Net-(U3-CP)") (class "Default")
      (node (ref "C53") (pin "2") (pinfunction "2_2") (pintype "passive"))
      (node (ref "R38") (pin "1") (pinfunction "1_1") (pintype "passive"))
      (node (ref "U3") (pin "15") (pinfunction "CP_15") (pintype "passive"))
    )
    (net (code "36") (name "Net-(U3-Det1)") (class "Default")
      (node (ref "C58") (pin "1") (pinfunction "1_1") (pintype "passive"))
      (node (ref "U3") (pin "4") (pinfunction "Det1_4") (pintype "passive"))
    )
    (net (code "37") (name "Net-(U3-Det2)") (class "Default")
      (node (ref "C59") (pin "1") (pinfunction "1_1") (pintype "passive"))
      (node (ref "U3") (pin "5") (pinfunction "Det2_5") (pintype "passive"))
    )
    (net (code "38") (name "Net-(U3-TF1N)") (class "Default")
      (node (ref "L4") (pin "1") (pinfunction "1_1") (pintype "passive"))
      (node (ref "U3") (pin "21") (pinfunction "TF1N_21") (pintype "passive"))
    )
    (net (code "39") (name "Net-(U3-TF1P)") (class "Default")
      (node (ref "L3") (pin "1") (pinfunction "1_1") (pintype "passive"))
      (node (ref "U3") (pin "22") (pinfunction "TF1P_22") (pintype "passive"))
    )
    (net (code "40") (name "Net-(U3-TF2N)") (class "Default")
      (node (ref "L4") (pin "2") (pinfunction "2_2") (pintype "passive"))
      (node (ref "U3") (pin "19") (pinfunction "TF2N_19") (pintype "passive"))
    )
    (net (code "41") (name "Net-(U3-TF2P)") (class "Default")
      (node (ref "L3") (pin "2") (pinfunction "2_2") (pintype "passive"))
      (node (ref "U3") (pin "20") (pinfunction "TF2P_20") (pintype "passive"))
    )
    (net (code "42") (name "Net-(U3-VDD_PLL)") (class "Default")
      (node (ref "C50") (pin "2") (pinfunction "2_2") (pintype "passive"))
      (node (ref "U3") (pin "17") (pinfunction "VDD_PLL_17") (pintype "passive"))
    )
    (net (code "43") (name "Net-(U3-Xtal_I)") (class "Default")
      (node (ref "C69") (pin "1") (pinfunction "1_1") (pintype "passive"))
      (node (ref "U3") (pin "8") (pinfunction "Xtal_I_8") (pintype "passive"))
      (node (ref "X1") (pin "1") (pinfunction "GND/NC_1") (pintype "passive"))
      (node (ref "X1") (pin "5") (pinfunction "5_5") (pintype "passive"))
    )
    (net (code "44") (name "Net-(U3-Xtal_O)") (class "Default")
      (node (ref "C70") (pin "1") (pinfunction "1_1") (pintype "passive"))
      (node (ref "U3") (pin "9") (pinfunction "Xtal_O_9") (pintype "passive"))
      (node (ref "X1") (pin "3") (pinfunction "OUT_3") (pintype "passive"))
      (node (ref "X1") (pin "6") (pinfunction "6_6") (pintype "passive"))
    )
    (net (code "45") (name "VBUS") (class "Default")
      (node (ref "C35") (pin "2") (pinfunction "2_2") (pintype "passive"))
      (node (ref "U1") (pin "3") (pinfunction "IN_3") (pintype "power_in"))
    )
    (net (code "46") (name "unconnected-(IC3-WP-Pad7)") (class "Default")
      (node (ref "IC3") (pin "7") (pinfunction "WP_7") (pintype "passive+no_connect"))
    )
    (net (code "47") (name "unconnected-(U2-AGC_RF-Pad15)") (class "Default")
      (node (ref "U2") (pin "15") (pinfunction "AGC_RF_15") (pintype "passive+no_connect"))
    )
    (net (code "48") (name "unconnected-(U2-GPIO0-Pad37)") (class "Default")
      (node (ref "U2") (pin "37") (pinfunction "GPIO0_37") (pintype "passive+no_connect"))
    )
    (net (code "49") (name "unconnected-(U2-GPIO1-Pad32)") (class "Default")
      (node (ref "U2") (pin "32") (pinfunction "GPIO1_32") (pintype "passive+no_connect"))
    )
    (net (code "50") (name "unconnected-(U2-GPIO2-Pad31)") (class "Default")
      (node (ref "U2") (pin "31") (pinfunction "GPIO2_31") (pintype "passive+no_connect"))
    )
    (net (code "51") (name "unconnected-(U2-GPIO3-Pad36)") (class "Default")
      (node (ref "U2") (pin "36") (pinfunction "GPIO3_36") (pintype "passive+no_connect"))
    )
    (net (code "52") (name "unconnected-(U2-GPIO4-Pad30)") (class "Default")
      (node (ref "U2") (pin "30") (pinfunction "GPIO4_30") (pintype "passive+no_connect"))
    )
    (net (code "53") (name "unconnected-(U2-GPIO5-Pad29)") (class "Default")
      (node (ref "U2") (pin "29") (pinfunction "GPIO5_29") (pintype "passive+no_connect"))
    )
    (net (code "54") (name "unconnected-(U2-GPIO6-Pad22)") (class "Default")
      (node (ref "U2") (pin "22") (pinfunction "GPIO6_22") (pintype "passive+no_connect"))
    )
    (net (code "55") (name "unconnected-(U2-GPIO7-Pad21)") (class "Default")
      (node (ref "U2") (pin "21") (pinfunction "GPIO7_21") (pintype "passive+no_connect"))
    )
    (net (code "56") (name "unconnected-(U2-IR_RX_IN-Pad38)") (class "Default")
      (node (ref "U2") (pin "38") (pinfunction "IR_RX_IN_38") (pintype "passive+no_connect"))
    )
    (net (code "57") (name "unconnected-(U2-M_ERR-Pad35)") (class "Default")
      (node (ref "U2") (pin "35") (pinfunction "M_ERR_35") (pintype "passive+no_connect"))
    )
    (net (code "58") (name "unconnected-(U2-TP_CKO-Pad9)") (class "Default")
      (node (ref "U2") (pin "9") (pinfunction "TP_CKO_9") (pintype "passive+no_connect"))
    )
    (net (code "59") (name "unconnected-(U2-VINR-Pad6)") (class "Default")
      (node (ref "U2") (pin "6") (pinfunction "VINR_6") (pintype "passive+no_connect"))
    )
    (net (code "60") (name "unconnected-(U2-VQN-Pad5)") (class "Default")
      (node (ref "U2") (pin "5") (pinfunction "VQN_5") (pintype "passive+no_connect"))
    )
    (net (code "61") (name "unconnected-(U2-VQP-Pad4)") (class "Default")
      (node (ref "U2") (pin "4") (pinfunction "VQP_4") (pintype "passive+no_connect"))
    )
    (net (code "62") (name "unconnected-(U3-Loop-Pad3)") (class "Default")
      (node (ref "U3") (pin "3") (pinfunction "Loop_3") (pintype "passive+no_connect"))
    )
    (net (code "63") (name "unconnected-(U3-NC-Pad1)") (class "Default")
      (node (ref "U3") (pin "1") (pinfunction "NC_1") (pintype "passive+no_connect"))
    )
  )
)
